# mcu_with_peripherals.net
KiCad netlist of a schematic drawn in Altium Designer
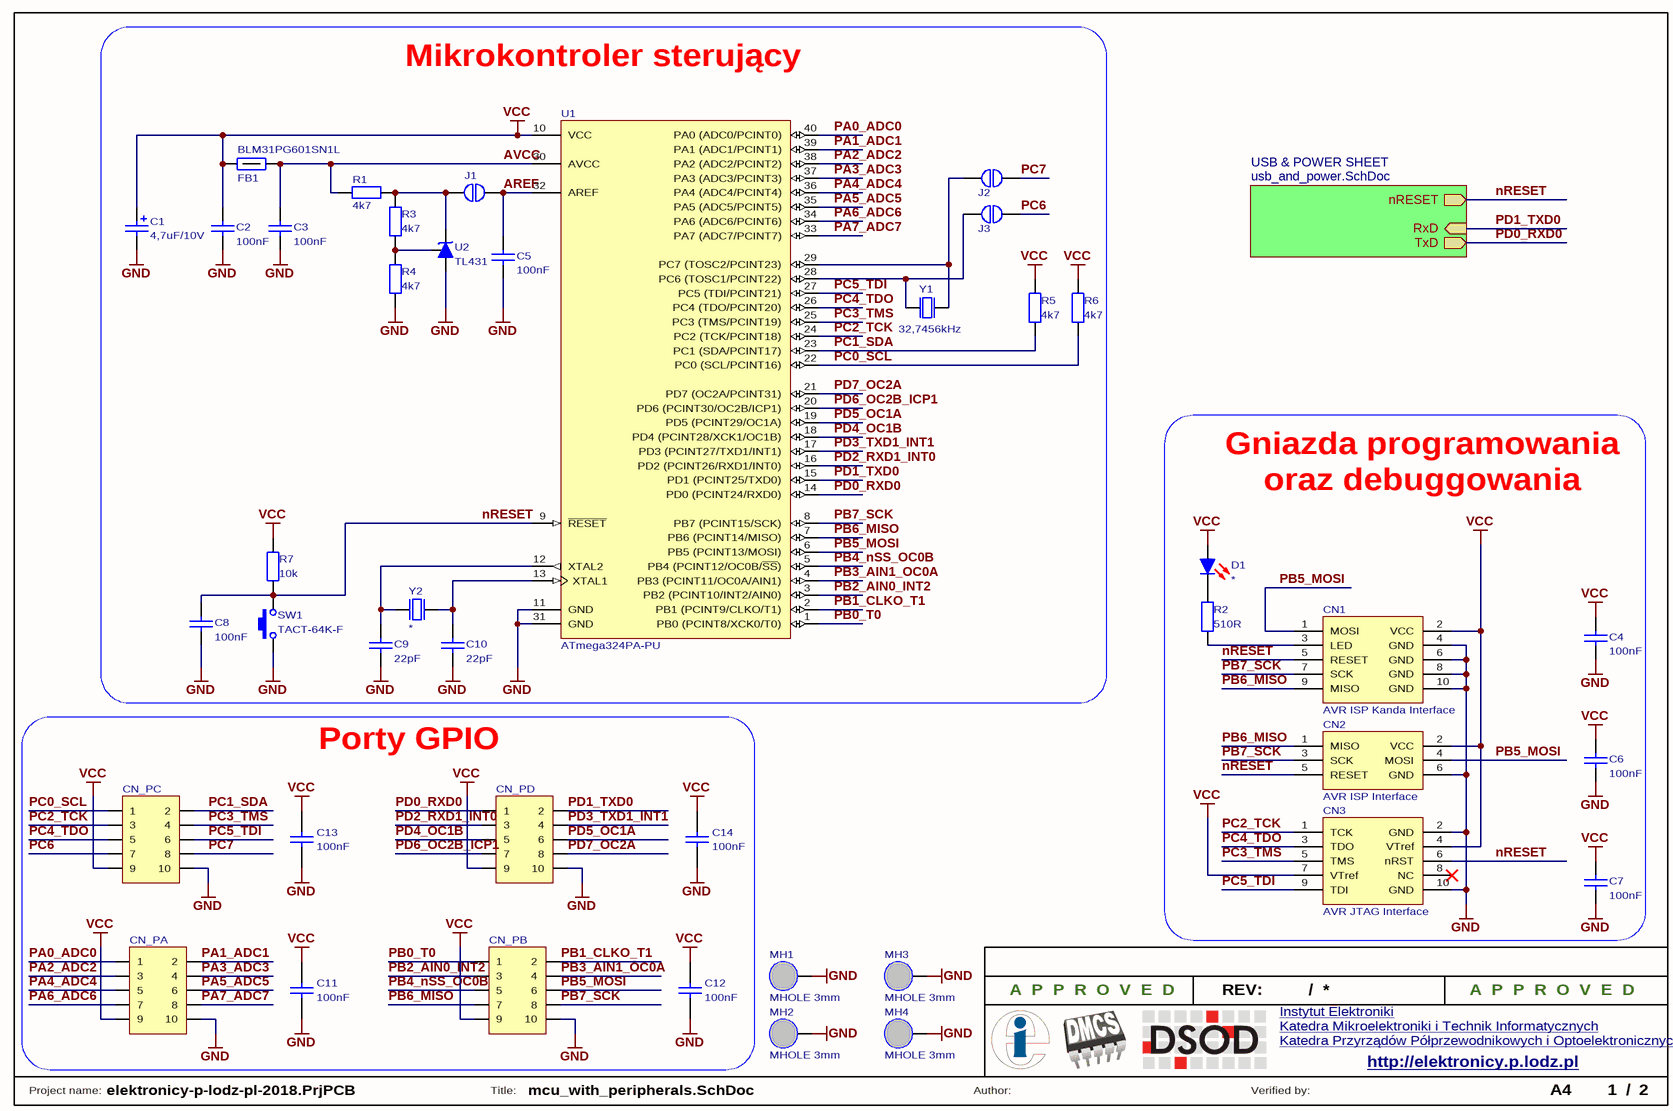
[diagram p0: mcu_with_peripherals.SchDoc]

(export (version "E")
  (design (tool "Eeschema 10.0.6"))
  (components
    (comp (ref "C1")
      (value "4,7uF/10V")
      (footprint "SMDB")
      (description "Polarized Tantalum Capacitor")
      (libsource (lib "capacitors") (part "Cap Pol Tant"))
    )
    (comp (ref "C2")
      (value "100nF")
      (footprint "C1206")
      (description "Capacitor")
      (libsource (lib "") (part "Cap_1"))
    )
    (comp (ref "C3")
      (value "100nF")
      (footprint "C1206")
      (description "Capacitor")
      (libsource (lib "") (part "Cap_1"))
    )
    (comp (ref "C4")
      (value "100nF")
      (footprint "C1206")
      (description "Capacitor")
      (libsource (lib "") (part "Cap_1"))
    )
    (comp (ref "C5")
      (value "100nF")
      (footprint "C1206")
      (description "Capacitor")
      (libsource (lib "") (part "Cap_1"))
    )
    (comp (ref "C6")
      (value "100nF")
      (footprint "C1206")
      (description "Capacitor")
      (libsource (lib "") (part "Cap_1"))
    )
    (comp (ref "C7")
      (value "100nF")
      (footprint "C1206")
      (description "Capacitor")
      (libsource (lib "") (part "Cap_1"))
    )
    (comp (ref "C8")
      (value "100nF")
      (footprint "C1206")
      (description "Capacitor")
      (libsource (lib "") (part "Cap_1"))
    )
    (comp (ref "C9")
      (value "22pF")
      (footprint "C1206")
      (description "Capacitor")
      (libsource (lib "") (part "Cap_1"))
    )
    (comp (ref "C10")
      (value "22pF")
      (footprint "C1206")
      (description "Capacitor")
      (libsource (lib "") (part "Cap_1"))
    )
    (comp (ref "C11")
      (value "100nF")
      (footprint "C1206")
      (description "Capacitor")
      (libsource (lib "capacitors") (part "Cap"))
    )
    (comp (ref "C12")
      (value "100nF")
      (footprint "C1206")
      (description "Capacitor")
      (libsource (lib "capacitors") (part "Cap"))
    )
    (comp (ref "C13")
      (value "100nF")
      (footprint "C1206")
      (description "Capacitor")
      (libsource (lib "capacitors") (part "Cap"))
    )
    (comp (ref "C14")
      (value "100nF")
      (footprint "C1206")
      (description "Capacitor")
      (libsource (lib "capacitors") (part "Cap"))
    )
    (comp (ref "CN1")
      (value "AVR ISP Kanda Interface")
      (footprint "IDC10")
      (description "Kanda ISP Programming Header for AVR MCU's")
      (libsource (lib "mcu_prog_and_debug_connectors") (part "AVR ISP Kanda Interface"))
    )
    (comp (ref "CN2")
      (value "AVR ISP Interface")
      (footprint "IDC6")
      (description "ISP Programming Header for AVR MCU's")
      (libsource (lib "mcu_prog_and_debug_connectors") (part "AVR ISP Interface"))
    )
    (comp (ref "CN3")
      (value "AVR JTAG Interface")
      (footprint "IDC10")
      (description "JTAG Header for AVR MCU's")
      (libsource (lib "mcu_prog_and_debug_connectors") (part "AVR JTAG Interface"))
    )
    (comp (ref "CN_PA") (value "IDC Connector") (footprint "IDC10") (libsource (lib "idc") (part "CN_5x2")))
    (comp (ref "CN_PB") (value "IDC Connector") (footprint "IDC10") (libsource (lib "idc") (part "CN_5x2")))
    (comp (ref "CN_PC") (value "IDC Connector") (footprint "IDC10") (libsource (lib "idc") (part "CN_5x2")))
    (comp (ref "CN_PD") (value "IDC Connector") (footprint "IDC10") (libsource (lib "idc") (part "CN_5x2")))
    (comp (ref "D1")
      (value "*")
      (footprint "LED1206R")
      (description "RED LED")
      (libsource (lib "leds") (part "LED_RED"))
    )
    (comp (ref "FB1")
      (value "BLM31PG601SN1L")
      (footprint "FB1206")
      (description "Ferrite Bead; Imp.@ 100MHz:600R; Mounting: SMD; 1,5A; Case: 1206")
      (libsource (lib "emi_emc_ferrites") (part "BLM31PG601SN1L"))
    )
    (comp (ref "J1")
      (value "*")
      (footprint "JMP2_0603_NO")
      (description "Solder Jumper - Open")
      (libsource (lib "jumpers_and_circuit_brakers") (part "JUMPER2_NO"))
    )
    (comp (ref "J2")
      (value "*")
      (footprint "JMP2_0603_NO")
      (description "Solder Jumper - Open")
      (libsource (lib "jumpers_and_circuit_brakers") (part "JUMPER2_NO"))
    )
    (comp (ref "J3")
      (value "*")
      (footprint "JMP2_0603_NO")
      (description "Solder Jumper - Open")
      (libsource (lib "jumpers_and_circuit_brakers") (part "JUMPER2_NO"))
    )
    (comp (ref "MH1")
      (value "MHOLE 3mm")
      (footprint "3mm screw drill III")
      (description "3mm Mounting Hole")
      (libsource (lib "mechanical_other") (part "MHOLE_3MM"))
    )
    (comp (ref "MH2")
      (value "MHOLE 3mm")
      (footprint "3mm screw drill III")
      (description "3mm Mounting Hole")
      (libsource (lib "mechanical_other") (part "MHOLE_3MM"))
    )
    (comp (ref "MH3")
      (value "MHOLE 3mm")
      (footprint "3mm screw drill III")
      (description "3mm Mounting Hole")
      (libsource (lib "mechanical_other") (part "MHOLE_3MM"))
    )
    (comp (ref "MH4")
      (value "MHOLE 3mm")
      (footprint "3mm screw drill III")
      (description "3mm Mounting Hole")
      (libsource (lib "mechanical_other") (part "MHOLE_3MM"))
    )
    (comp (ref "R1")
      (value "4k7")
      (footprint "R1206")
      (description "Resistor")
      (libsource (lib "") (part "Res_2"))
    )
    (comp (ref "R2")
      (value "510R")
      (footprint "R1206")
      (description "Resistor")
      (libsource (lib "resistors") (part "Res"))
    )
    (comp (ref "R3")
      (value "4k7")
      (footprint "R1206")
      (description "Resistor")
      (libsource (lib "") (part "Res_1"))
    )
    (comp (ref "R4")
      (value "4k7")
      (footprint "R1206")
      (description "Resistor")
      (libsource (lib "") (part "Res_1"))
    )
    (comp (ref "R5")
      (value "4k7")
      (footprint "R1206")
      (description "Resistor")
      (libsource (lib "resistors") (part "Res"))
    )
    (comp (ref "R6")
      (value "4k7")
      (footprint "R1206")
      (description "Resistor")
      (libsource (lib "resistors") (part "Res"))
    )
    (comp (ref "R7")
      (value "10k")
      (footprint "R1206")
      (description "Resistor")
      (libsource (lib "resistors") (part "Res"))
    )
    (comp (ref "SW1")
      (value "TACT-64K-F")
      (footprint "TACT-64K-F")
      (description "6x6mm THT Tactile SPST-NO Switch")
      (libsource (lib "microswitches") (part "TACT-64K-F"))
    )
    (comp (ref "U1")
      (value "ATmega324PA-PU")
      (footprint "DIP40_PRECISION_W_IC")
      (libsource (lib "mcus_atmel") (part "ATmega324PA-PU"))
    )
    (comp (ref "U2")
      (value "TL431")
      (footprint "SOT-23")
      (description "0,5% Precision Programmable Reference")
      (libsource (lib "reference_voltage_sources") (part "TL431BCDBZ"))
    )
    (comp (ref "Y1")
      (value "32,7456kHz")
      (footprint "TC38_3x8_H")
      (description "Crystal Clock Oscillator")
      (libsource (lib "quartz_crystals_and_filters") (part "Clock XTAL"))
    )
    (comp (ref "Y2")
      (value "*")
      (footprint "HC49-S")
      (description "Crystal Oscillator")
      (libsource (lib "quartz_crystals_and_filters") (part "XTAL_2PIN"))
    )
  )
  (nets
    (net (code "1") (name "/AREF") (class "Default")
      (node (ref "C5") (pin "2") (pinfunction "2_2") (pintype "passive"))
      (node (ref "J1") (pin "2") (pinfunction "2_2") (pintype "passive"))
      (node (ref "U1") (pin "32") (pinfunction "AREF_32") (pintype "power_in"))
    )
    (net (code "2") (name "/AVCC") (class "Default")
      (node (ref "C3") (pin "2") (pinfunction "2_2") (pintype "passive"))
      (node (ref "FB1") (pin "2") (pinfunction "2_2") (pintype "passive"))
      (node (ref "R1") (pin "1") (pinfunction "1_1") (pintype "passive"))
      (node (ref "U1") (pin "30") (pinfunction "AVCC_30") (pintype "power_in"))
    )
    (net (code "3") (name "/PA0_ADC0") (class "Default")
      (node (ref "CN_PA") (pin "1") (pinfunction "1_1") (pintype "passive"))
      (node (ref "U1") (pin "40") (pinfunction "PA0_(ADC0/PCINT0)_40") (pintype "bidirectional"))
    )
    (net (code "4") (name "/PA1_ADC1") (class "Default")
      (node (ref "CN_PA") (pin "2") (pinfunction "2_2") (pintype "passive"))
      (node (ref "U1") (pin "39") (pinfunction "PA1_(ADC1/PCINT1)_39") (pintype "bidirectional"))
    )
    (net (code "5") (name "/PA2_ADC2") (class "Default")
      (node (ref "CN_PA") (pin "3") (pinfunction "3_3") (pintype "passive"))
      (node (ref "U1") (pin "38") (pinfunction "PA2_(ADC2/PCINT2)_38") (pintype "bidirectional"))
    )
    (net (code "6") (name "/PA3_ADC3") (class "Default")
      (node (ref "CN_PA") (pin "4") (pinfunction "4_4") (pintype "passive"))
      (node (ref "U1") (pin "37") (pinfunction "PA3_(ADC3/PCINT3)_37") (pintype "bidirectional"))
    )
    (net (code "7") (name "/PA4_ADC4") (class "Default")
      (node (ref "CN_PA") (pin "5") (pinfunction "5_5") (pintype "passive"))
      (node (ref "U1") (pin "36") (pinfunction "PA4_(ADC4/PCINT4)_36") (pintype "bidirectional"))
    )
    (net (code "8") (name "/PA5_ADC5") (class "Default")
      (node (ref "CN_PA") (pin "6") (pinfunction "6_6") (pintype "passive"))
      (node (ref "U1") (pin "35") (pinfunction "PA5_(ADC5/PCINT5)_35") (pintype "bidirectional"))
    )
    (net (code "9") (name "/PA6_ADC6") (class "Default")
      (node (ref "CN_PA") (pin "7") (pinfunction "7_7") (pintype "passive"))
      (node (ref "U1") (pin "34") (pinfunction "PA6_(ADC6/PCINT6)_34") (pintype "bidirectional"))
    )
    (net (code "10") (name "/PA7_ADC7") (class "Default")
      (node (ref "CN_PA") (pin "8") (pinfunction "8_8") (pintype "passive"))
      (node (ref "U1") (pin "33") (pinfunction "PA7_(ADC7/PCINT7)_33") (pintype "bidirectional"))
    )
    (net (code "11") (name "/PB0_T0") (class "Default")
      (node (ref "CN_PB") (pin "1") (pinfunction "1_1") (pintype "passive"))
      (node (ref "U1") (pin "1") (pinfunction "PB0_(PCINT8/XCK0/T0)_1") (pintype "bidirectional"))
    )
    (net (code "12") (name "/PB1_CLKO_T1") (class "Default")
      (node (ref "CN_PB") (pin "2") (pinfunction "2_2") (pintype "passive"))
      (node (ref "U1") (pin "2") (pinfunction "PB1_(PCINT9/CLKO/T1)_2") (pintype "bidirectional"))
    )
    (net (code "13") (name "/PB2_AIN0_INT2") (class "Default")
      (node (ref "CN_PB") (pin "3") (pinfunction "3_3") (pintype "passive"))
      (node (ref "U1") (pin "3") (pinfunction "PB2_(PCINT10/INT2/AIN0)_3") (pintype "bidirectional"))
    )
    (net (code "14") (name "/PB3_AIN1_OC0A") (class "Default")
      (node (ref "CN_PB") (pin "4") (pinfunction "4_4") (pintype "passive"))
      (node (ref "U1") (pin "4") (pinfunction "PB3_(PCINT11/OC0A/AIN1)_4") (pintype "bidirectional"))
    )
    (net (code "15") (name "/PB4_nSS_OC0B") (class "Default")
      (node (ref "CN_PB") (pin "5") (pinfunction "5_5") (pintype "passive"))
      (node (ref "U1") (pin "5") (pinfunction "PB4_(PCINT12/OC0B/~{SS})_5") (pintype "bidirectional"))
    )
    (net (code "16") (name "/PB5_MOSI") (class "Default")
      (node (ref "CN1") (pin "1") (pinfunction "MOSI_1") (pintype "passive"))
      (node (ref "CN2") (pin "4") (pinfunction "MOSI_4") (pintype "passive"))
      (node (ref "CN_PB") (pin "6") (pinfunction "6_6") (pintype "passive"))
      (node (ref "U1") (pin "6") (pinfunction "PB5_(PCINT13/MOSI)_6") (pintype "bidirectional"))
    )
    (net (code "17") (name "/PB6_MISO") (class "Default")
      (node (ref "CN1") (pin "9") (pinfunction "MISO_9") (pintype "passive"))
      (node (ref "CN2") (pin "1") (pinfunction "MISO_1") (pintype "passive"))
      (node (ref "CN_PB") (pin "7") (pinfunction "7_7") (pintype "passive"))
      (node (ref "U1") (pin "7") (pinfunction "PB6_(PCINT14/MISO)_7") (pintype "bidirectional"))
    )
    (net (code "18") (name "/PB7_SCK") (class "Default")
      (node (ref "CN1") (pin "7") (pinfunction "SCK_7") (pintype "passive"))
      (node (ref "CN2") (pin "3") (pinfunction "SCK_3") (pintype "passive"))
      (node (ref "CN_PB") (pin "8") (pinfunction "8_8") (pintype "passive"))
      (node (ref "U1") (pin "8") (pinfunction "PB7_(PCINT15/SCK)_8") (pintype "bidirectional"))
    )
    (net (code "19") (name "/PC0_SCL") (class "Default")
      (node (ref "CN_PC") (pin "1") (pinfunction "1_1") (pintype "passive"))
      (node (ref "R6") (pin "1") (pinfunction "1_1") (pintype "passive"))
      (node (ref "U1") (pin "22") (pinfunction "PC0_(SCL/PCINT16)_22") (pintype "bidirectional"))
    )
    (net (code "20") (name "/PC1_SDA") (class "Default")
      (node (ref "CN_PC") (pin "2") (pinfunction "2_2") (pintype "passive"))
      (node (ref "R5") (pin "1") (pinfunction "1_1") (pintype "passive"))
      (node (ref "U1") (pin "23") (pinfunction "PC1_(SDA/PCINT17)_23") (pintype "bidirectional"))
    )
    (net (code "21") (name "/PC2_TCK") (class "Default")
      (node (ref "CN3") (pin "1") (pinfunction "TCK_1") (pintype "passive"))
      (node (ref "CN_PC") (pin "3") (pinfunction "3_3") (pintype "passive"))
      (node (ref "U1") (pin "24") (pinfunction "PC2_(TCK/PCINT18)_24") (pintype "bidirectional"))
    )
    (net (code "22") (name "/PC3_TMS") (class "Default")
      (node (ref "CN3") (pin "5") (pinfunction "TMS_5") (pintype "passive"))
      (node (ref "CN_PC") (pin "4") (pinfunction "4_4") (pintype "passive"))
      (node (ref "U1") (pin "25") (pinfunction "PC3_(TMS/PCINT19)_25") (pintype "bidirectional"))
    )
    (net (code "23") (name "/PC4_TDO") (class "Default")
      (node (ref "CN3") (pin "3") (pinfunction "TDO_3") (pintype "passive"))
      (node (ref "CN_PC") (pin "5") (pinfunction "5_5") (pintype "passive"))
      (node (ref "U1") (pin "26") (pinfunction "PC4_(TDO/PCINT20)_26") (pintype "bidirectional"))
    )
    (net (code "24") (name "/PC5_TDI") (class "Default")
      (node (ref "CN3") (pin "9") (pinfunction "TDI_9") (pintype "passive"))
      (node (ref "CN_PC") (pin "6") (pinfunction "6_6") (pintype "passive"))
      (node (ref "U1") (pin "27") (pinfunction "PC5_(TDI/PCINT21)_27") (pintype "bidirectional"))
    )
    (net (code "25") (name "/PC6") (class "Default")
      (node (ref "CN_PC") (pin "7") (pinfunction "7_7") (pintype "passive"))
      (node (ref "J3") (pin "2") (pinfunction "2_2") (pintype "passive"))
    )
    (net (code "26") (name "/PC7") (class "Default")
      (node (ref "CN_PC") (pin "8") (pinfunction "8_8") (pintype "passive"))
      (node (ref "J2") (pin "2") (pinfunction "2_2") (pintype "passive"))
    )
    (net (code "27") (name "/PD0_RXD0") (class "Default")
      (node (ref "CN_PD") (pin "1") (pinfunction "1_1") (pintype "passive"))
      (node (ref "U1") (pin "14") (pinfunction "PD0_(PCINT24/RXD0)_14") (pintype "bidirectional"))
    )
    (net (code "28") (name "/PD1_TXD0") (class "Default")
      (node (ref "CN_PD") (pin "2") (pinfunction "2_2") (pintype "passive"))
      (node (ref "U1") (pin "15") (pinfunction "PD1_(PCINT25/TXD0)_15") (pintype "bidirectional"))
    )
    (net (code "29") (name "/PD2_RXD1_INT0") (class "Default")
      (node (ref "CN_PD") (pin "3") (pinfunction "3_3") (pintype "passive"))
      (node (ref "U1") (pin "16") (pinfunction "PD2_(PCINT26/RXD1/INT0)_16") (pintype "bidirectional"))
    )
    (net (code "30") (name "/PD3_TXD1_INT1") (class "Default")
      (node (ref "CN_PD") (pin "4") (pinfunction "4_4") (pintype "passive"))
      (node (ref "U1") (pin "17") (pinfunction "PD3_(PCINT27/TXD1/INT1)_17") (pintype "bidirectional"))
    )
    (net (code "31") (name "/PD4_OC1B") (class "Default")
      (node (ref "CN_PD") (pin "5") (pinfunction "5_5") (pintype "passive"))
      (node (ref "U1") (pin "18") (pinfunction "PD4_(PCINT28/XCK1/OC1B)_18") (pintype "bidirectional"))
    )
    (net (code "32") (name "/PD5_OC1A") (class "Default")
      (node (ref "CN_PD") (pin "6") (pinfunction "6_6") (pintype "passive"))
      (node (ref "U1") (pin "19") (pinfunction "PD5_(PCINT29/OC1A)_19") (pintype "bidirectional"))
    )
    (net (code "33") (name "/PD6_OC2B_ICP1") (class "Default")
      (node (ref "CN_PD") (pin "7") (pinfunction "7_7") (pintype "passive"))
      (node (ref "U1") (pin "20") (pinfunction "PD6_(PCINT30/OC2B/ICP1)_20") (pintype "bidirectional"))
    )
    (net (code "34") (name "/PD7_OC2A") (class "Default")
      (node (ref "CN_PD") (pin "8") (pinfunction "8_8") (pintype "passive"))
      (node (ref "U1") (pin "21") (pinfunction "PD7_(OC2A/PCINT31)_21") (pintype "bidirectional"))
    )
    (net (code "35") (name "/nRESET") (class "Default")
      (node (ref "C8") (pin "2") (pinfunction "2_2") (pintype "passive"))
      (node (ref "CN1") (pin "5") (pinfunction "RESET_5") (pintype "passive"))
      (node (ref "CN2") (pin "5") (pinfunction "RESET_5") (pintype "passive"))
      (node (ref "CN3") (pin "6") (pinfunction "nRST_6") (pintype "passive"))
      (node (ref "R7") (pin "1") (pinfunction "1_1") (pintype "passive"))
      (node (ref "SW1") (pin "2") (pinfunction "2_2") (pintype "passive"))
      (node (ref "U1") (pin "9") (pinfunction "~{RESET}_9") (pintype "input"))
    )
    (net (code "36") (name "GND") (class "Default")
      (node (ref "C1") (pin "2") (pinfunction "2_2") (pintype "passive"))
      (node (ref "C10") (pin "1") (pinfunction "1_1") (pintype "passive"))
      (node (ref "C11") (pin "1") (pinfunction "1_1") (pintype "passive"))
      (node (ref "C12") (pin "1") (pinfunction "1_1") (pintype "passive"))
      (node (ref "C13") (pin "1") (pinfunction "1_1") (pintype "passive"))
      (node (ref "C14") (pin "1") (pinfunction "1_1") (pintype "passive"))
      (node (ref "C2") (pin "1") (pinfunction "1_1") (pintype "passive"))
      (node (ref "C3") (pin "1") (pinfunction "1_1") (pintype "passive"))
      (node (ref "C4") (pin "1") (pinfunction "1_1") (pintype "passive"))
      (node (ref "C5") (pin "1") (pinfunction "1_1") (pintype "passive"))
      (node (ref "C6") (pin "1") (pinfunction "1_1") (pintype "passive"))
      (node (ref "C7") (pin "1") (pinfunction "1_1") (pintype "passive"))
      (node (ref "C8") (pin "1") (pinfunction "1_1") (pintype "passive"))
      (node (ref "C9") (pin "1") (pinfunction "1_1") (pintype "passive"))
      (node (ref "CN1") (pin "10") (pinfunction "GND_10") (pintype "passive"))
      (node (ref "CN1") (pin "4") (pinfunction "GND_4") (pintype "passive"))
      (node (ref "CN1") (pin "6") (pinfunction "GND_6") (pintype "passive"))
      (node (ref "CN1") (pin "8") (pinfunction "GND_8") (pintype "passive"))
      (node (ref "CN2") (pin "6") (pinfunction "GND_6") (pintype "passive"))
      (node (ref "CN3") (pin "10") (pinfunction "GND_10") (pintype "passive"))
      (node (ref "CN3") (pin "2") (pinfunction "GND_2") (pintype "passive"))
      (node (ref "CN_PA") (pin "10") (pinfunction "10_10") (pintype "passive"))
      (node (ref "CN_PB") (pin "10") (pinfunction "10_10") (pintype "passive"))
      (node (ref "CN_PC") (pin "10") (pinfunction "10_10") (pintype "passive"))
      (node (ref "CN_PD") (pin "10") (pinfunction "10_10") (pintype "passive"))
      (node (ref "MH1") (pin "1") (pinfunction "GND_1") (pintype "passive"))
      (node (ref "MH2") (pin "1") (pinfunction "GND_1") (pintype "passive"))
      (node (ref "MH3") (pin "1") (pinfunction "GND_1") (pintype "passive"))
      (node (ref "MH4") (pin "1") (pinfunction "GND_1") (pintype "passive"))
      (node (ref "R4") (pin "2") (pinfunction "2_2") (pintype "passive"))
      (node (ref "SW1") (pin "1") (pinfunction "1_1") (pintype "passive"))
      (node (ref "U1") (pin "11") (pinfunction "GND_11") (pintype "power_in"))
      (node (ref "U1") (pin "31") (pinfunction "GND_31") (pintype "power_in"))
      (node (ref "U2") (pin "3") (pinfunction "A_3") (pintype "passive"))
    )
    (net (code "37") (name "Net-(CN1-LED)") (class "Default")
      (node (ref "CN1") (pin "3") (pinfunction "LED_3") (pintype "passive"))
      (node (ref "R2") (pin "1") (pinfunction "1_1") (pintype "passive"))
    )
    (net (code "38") (name "Net-(D1-K)") (class "Default")
      (node (ref "D1") (pin "2") (pinfunction "K_2") (pintype "passive"))
      (node (ref "R2") (pin "2") (pinfunction "2_2") (pintype "passive"))
    )
    (net (code "39") (name "Net-(U1-PC6_(TOSC1{slash}PCINT22))") (class "Default")
      (node (ref "J3") (pin "1") (pinfunction "1_1") (pintype "passive"))
      (node (ref "U1") (pin "28") (pinfunction "PC6_(TOSC1/PCINT22)_28") (pintype "bidirectional"))
      (node (ref "Y1") (pin "2") (pinfunction "OSC2_2") (pintype "passive"))
    )
    (net (code "40") (name "Net-(U1-PC7_(TOSC2{slash}PCINT23))") (class "Default")
      (node (ref "J2") (pin "1") (pinfunction "1_1") (pintype "passive"))
      (node (ref "U1") (pin "29") (pinfunction "PC7_(TOSC2/PCINT23)_29") (pintype "bidirectional"))
      (node (ref "Y1") (pin "1") (pinfunction "OSC1_1") (pintype "passive"))
    )
    (net (code "41") (name "Net-(U1-XTAL1)") (class "Default")
      (node (ref "C10") (pin "2") (pinfunction "2_2") (pintype "passive"))
      (node (ref "U1") (pin "13") (pinfunction "XTAL1_13") (pintype "input"))
      (node (ref "Y2") (pin "2") (pinfunction "OSC2_2") (pintype "passive"))
    )
    (net (code "42") (name "Net-(U1-XTAL2)") (class "Default")
      (node (ref "C9") (pin "2") (pinfunction "2_2") (pintype "passive"))
      (node (ref "U1") (pin "12") (pinfunction "XTAL2_12") (pintype "output"))
      (node (ref "Y2") (pin "1") (pinfunction "OSC1_1") (pintype "passive"))
    )
    (net (code "43") (name "Net-(U2-K)") (class "Default")
      (node (ref "J1") (pin "1") (pinfunction "1_1") (pintype "passive"))
      (node (ref "R1") (pin "2") (pinfunction "2_2") (pintype "passive"))
      (node (ref "R3") (pin "1") (pinfunction "1_1") (pintype "passive"))
      (node (ref "U2") (pin "1") (pinfunction "K_1") (pintype "passive"))
    )
    (net (code "44") (name "Net-(U2-REF)") (class "Default")
      (node (ref "R3") (pin "2") (pinfunction "2_2") (pintype "passive"))
      (node (ref "R4") (pin "1") (pinfunction "1_1") (pintype "passive"))
      (node (ref "U2") (pin "2") (pinfunction "REF_2") (pintype "passive"))
    )
    (net (code "45") (name "VCC") (class "Default")
      (node (ref "C1") (pin "1") (pinfunction "1_1") (pintype "passive"))
      (node (ref "C11") (pin "2") (pinfunction "2_2") (pintype "passive"))
      (node (ref "C12") (pin "2") (pinfunction "2_2") (pintype "passive"))
      (node (ref "C13") (pin "2") (pinfunction "2_2") (pintype "passive"))
      (node (ref "C14") (pin "2") (pinfunction "2_2") (pintype "passive"))
      (node (ref "C2") (pin "2") (pinfunction "2_2") (pintype "passive"))
      (node (ref "C4") (pin "2") (pinfunction "2_2") (pintype "passive"))
      (node (ref "C6") (pin "2") (pinfunction "2_2") (pintype "passive"))
      (node (ref "C7") (pin "2") (pinfunction "2_2") (pintype "passive"))
      (node (ref "CN1") (pin "2") (pinfunction "VCC_2") (pintype "passive"))
      (node (ref "CN2") (pin "2") (pinfunction "VCC_2") (pintype "passive"))
      (node (ref "CN3") (pin "4") (pinfunction "VTref_4") (pintype "passive"))
      (node (ref "CN3") (pin "7") (pinfunction "VTref_7") (pintype "passive"))
      (node (ref "CN_PA") (pin "9") (pinfunction "9_9") (pintype "passive"))
      (node (ref "CN_PB") (pin "9") (pinfunction "9_9") (pintype "passive"))
      (node (ref "CN_PC") (pin "9") (pinfunction "9_9") (pintype "passive"))
      (node (ref "CN_PD") (pin "9") (pinfunction "9_9") (pintype "passive"))
      (node (ref "D1") (pin "1") (pinfunction "A_1") (pintype "passive"))
      (node (ref "FB1") (pin "1") (pinfunction "1_1") (pintype "passive"))
      (node (ref "R5") (pin "2") (pinfunction "2_2") (pintype "passive"))
      (node (ref "R6") (pin "2") (pinfunction "2_2") (pintype "passive"))
      (node (ref "R7") (pin "2") (pinfunction "2_2") (pintype "passive"))
      (node (ref "U1") (pin "10") (pinfunction "VCC_10") (pintype "power_in"))
    )
    (net (code "46") (name "unconnected-(CN3-NC-Pad8)") (class "Default")
      (node (ref "CN3") (pin "8") (pinfunction "NC_8") (pintype "passive+no_connect"))
    )
  )
)
